# Micro.net
KiCad netlist of a schematic drawn in Altium Designer
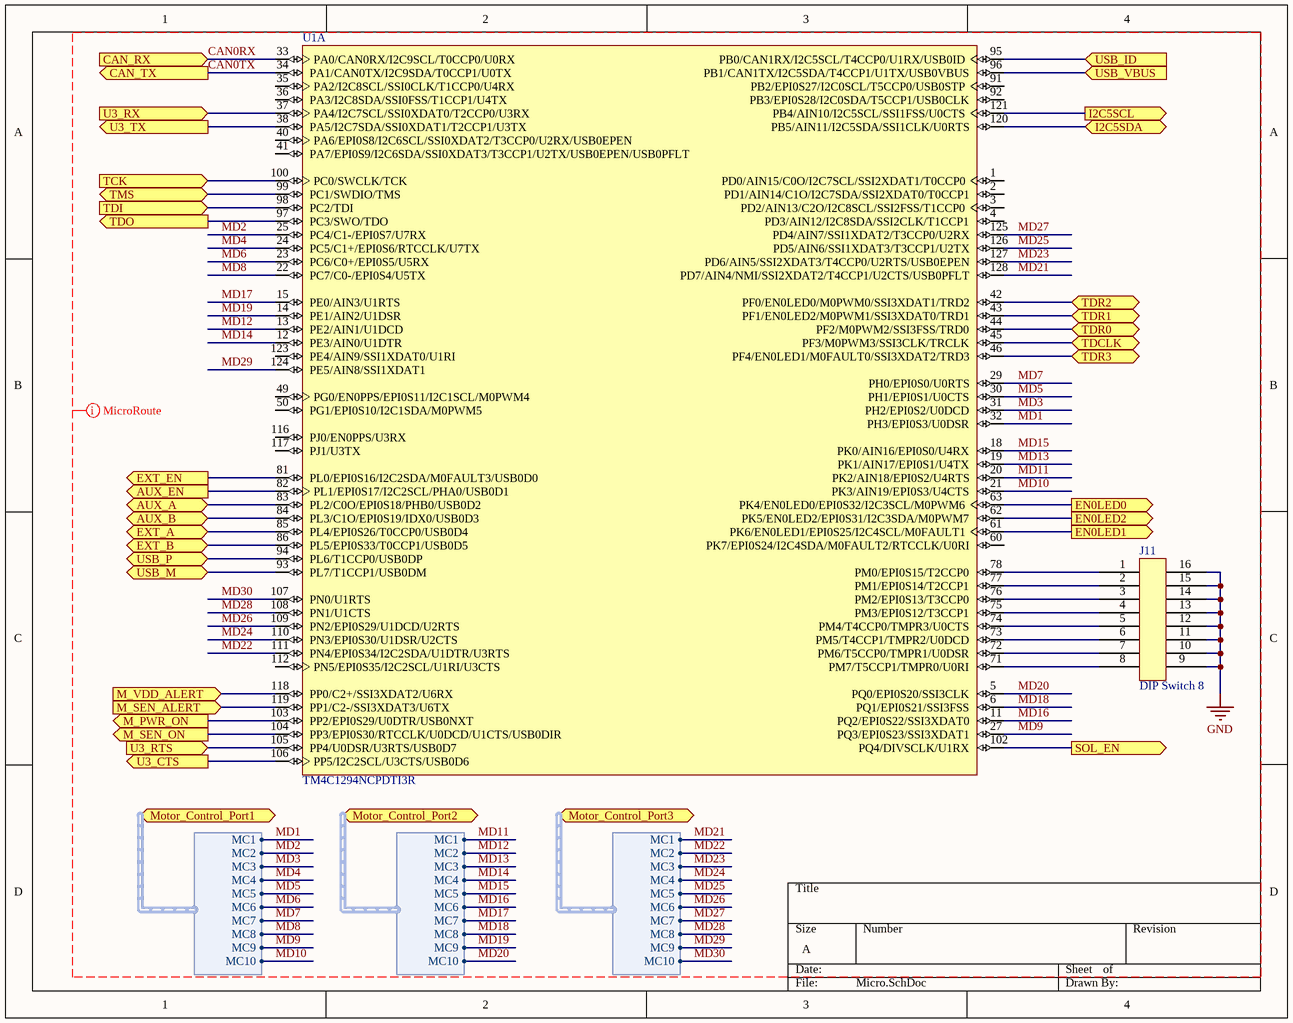
[diagram p0: Micro.SchDoc]

(export (version "E")
  (design (tool "Eeschema 10.0.6"))
  (components
    (comp (ref "J11") (value "DIP Switch 8") (footprint "DIP8") (libsource (lib "HSBNE-MAIN") (part "DIP8")))
    (comp (ref "U1")
      (value "TM4C1294NCPDTI3R")
      (footprint "TI-PDT128_M")
      (fields (field (name "MANUFACTURER") "Texas Instruments"))
      (libsource (lib "Altium Inc") (part "TI-TM4C1294NCPDT-128"))
    )
  )
  (nets
    (net (code "2") (name "/AUX_A") (class "Default")
      (node (ref "U1") (pin "83") (pinfunction "PL2/C0O/EPI0S18/PHB0/USB0D2_83") (pintype "bidirectional"))
    )
    (net (code "3") (name "/AUX_B") (class "Default")
      (node (ref "U1") (pin "84") (pinfunction "PL3/C1O/EPI0S19/IDX0/USB0D3_84") (pintype "bidirectional"))
    )
    (net (code "4") (name "/AUX_EN") (class "Default")
      (node (ref "U1") (pin "82") (pinfunction "PL1/EPI0S17/I2C2SCL/PHA0/USB0D1_82") (pintype "bidirectional"))
    )
    (net (code "5") (name "/CAN0RX") (class "Default")
      (node (ref "U1") (pin "33") (pinfunction "PA0/CAN0RX/I2C9SCL/T0CCP0/U0RX_33") (pintype "bidirectional"))
    )
    (net (code "6") (name "/CAN0TX") (class "Default")
      (node (ref "U1") (pin "34") (pinfunction "PA1/CAN0TX/I2C9SDA/T0CCP1/U0TX_34") (pintype "bidirectional"))
    )
    (net (code "7") (name "/EN0LED0") (class "Default")
      (node (ref "U1") (pin "63") (pinfunction "PK4/EN0LED0/EPI0S32/I2C3SCL/M0PWM6_63") (pintype "bidirectional"))
    )
    (net (code "8") (name "/EN0LED1") (class "Default")
      (node (ref "U1") (pin "61") (pinfunction "PK6/EN0LED1/EPI0S25/I2C4SCL/M0FAULT1_61") (pintype "bidirectional"))
    )
    (net (code "9") (name "/EN0LED2") (class "Default")
      (node (ref "U1") (pin "62") (pinfunction "PK5/EN0LED2/EPI0S31/I2C3SDA/M0PWM7_62") (pintype "bidirectional"))
    )
    (net (code "10") (name "/EXT_A") (class "Default")
      (node (ref "U1") (pin "85") (pinfunction "PL4/EPI0S26/T0CCP0/USB0D4_85") (pintype "bidirectional"))
    )
    (net (code "11") (name "/EXT_B") (class "Default")
      (node (ref "U1") (pin "86") (pinfunction "PL5/EPI0S33/T0CCP1/USB0D5_86") (pintype "bidirectional"))
    )
    (net (code "12") (name "/EXT_EN") (class "Default")
      (node (ref "U1") (pin "81") (pinfunction "PL0/EPI0S16/I2C2SDA/M0FAULT3/USB0D0_81") (pintype "bidirectional"))
    )
    (net (code "13") (name "/I2C5SCL") (class "Default")
      (node (ref "U1") (pin "121") (pinfunction "PB4/AIN10/I2C5SCL/SSI1FSS/U0CTS_121") (pintype "bidirectional"))
    )
    (net (code "14") (name "/I2C5SDA") (class "Default")
      (node (ref "U1") (pin "120") (pinfunction "PB5/AIN11/I2C5SDA/SSI1CLK/U0RTS_120") (pintype "bidirectional"))
    )
    (net (code "15") (name "/MD1") (class "Default")
      (node (ref "U1") (pin "32") (pinfunction "PH3/EPI0S3/U0DSR_32") (pintype "bidirectional"))
    )
    (net (code "16") (name "/MD2") (class "Default")
      (node (ref "U1") (pin "25") (pinfunction "PC4/C1-/EPI0S7/U7RX_25") (pintype "bidirectional"))
    )
    (net (code "17") (name "/MD3") (class "Default")
      (node (ref "U1") (pin "31") (pinfunction "PH2/EPI0S2/U0DCD_31") (pintype "bidirectional"))
    )
    (net (code "18") (name "/MD4") (class "Default")
      (node (ref "U1") (pin "24") (pinfunction "PC5/C1+/EPI0S6/RTCCLK/U7TX_24") (pintype "bidirectional"))
    )
    (net (code "19") (name "/MD5") (class "Default")
      (node (ref "U1") (pin "30") (pinfunction "PH1/EPI0S1/U0CTS_30") (pintype "bidirectional"))
    )
    (net (code "20") (name "/MD6") (class "Default")
      (node (ref "U1") (pin "23") (pinfunction "PC6/C0+/EPI0S5/U5RX_23") (pintype "bidirectional"))
    )
    (net (code "21") (name "/MD7") (class "Default")
      (node (ref "U1") (pin "29") (pinfunction "PH0/EPI0S0/U0RTS_29") (pintype "bidirectional"))
    )
    (net (code "22") (name "/MD8") (class "Default")
      (node (ref "U1") (pin "22") (pinfunction "PC7/C0-/EPI0S4/U5TX_22") (pintype "bidirectional"))
    )
    (net (code "23") (name "/MD9") (class "Default")
      (node (ref "U1") (pin "27") (pinfunction "PQ3/EPI0S23/SSI3XDAT1_27") (pintype "bidirectional"))
    )
    (net (code "24") (name "/MD10") (class "Default")
      (node (ref "U1") (pin "21") (pinfunction "PK3/AIN19/EPI0S3/U4CTS_21") (pintype "bidirectional"))
    )
    (net (code "25") (name "/MD11") (class "Default")
      (node (ref "U1") (pin "20") (pinfunction "PK2/AIN18/EPI0S2/U4RTS_20") (pintype "bidirectional"))
    )
    (net (code "26") (name "/MD12") (class "Default")
      (node (ref "U1") (pin "13") (pinfunction "PE2/AIN1/U1DCD_13") (pintype "bidirectional"))
    )
    (net (code "27") (name "/MD13") (class "Default")
      (node (ref "U1") (pin "19") (pinfunction "PK1/AIN17/EPI0S1/U4TX_19") (pintype "bidirectional"))
    )
    (net (code "28") (name "/MD14") (class "Default")
      (node (ref "U1") (pin "12") (pinfunction "PE3/AIN0/U1DTR_12") (pintype "bidirectional"))
    )
    (net (code "29") (name "/MD15") (class "Default")
      (node (ref "U1") (pin "18") (pinfunction "PK0/AIN16/EPI0S0/U4RX_18") (pintype "bidirectional"))
    )
    (net (code "30") (name "/MD16") (class "Default")
      (node (ref "U1") (pin "11") (pinfunction "PQ2/EPI0S22/SSI3XDAT0_11") (pintype "bidirectional"))
    )
    (net (code "31") (name "/MD17") (class "Default")
      (node (ref "U1") (pin "15") (pinfunction "PE0/AIN3/U1RTS_15") (pintype "bidirectional"))
    )
    (net (code "32") (name "/MD18") (class "Default")
      (node (ref "U1") (pin "6") (pinfunction "PQ1/EPI0S21/SSI3FSS_6") (pintype "bidirectional"))
    )
    (net (code "33") (name "/MD19") (class "Default")
      (node (ref "U1") (pin "14") (pinfunction "PE1/AIN2/U1DSR_14") (pintype "bidirectional"))
    )
    (net (code "34") (name "/MD20") (class "Default")
      (node (ref "U1") (pin "5") (pinfunction "PQ0/EPI0S20/SSI3CLK_5") (pintype "bidirectional"))
    )
    (net (code "35") (name "/MD21") (class "Default")
      (node (ref "U1") (pin "128") (pinfunction "PD7/AIN4/NMI/SSI2XDAT2/T4CCP1/U2CTS/USB0PFLT_128") (pintype "bidirectional"))
    )
    (net (code "36") (name "/MD22") (class "Default")
      (node (ref "U1") (pin "111") (pinfunction "PN4/EPI0S34/I2C2SDA/U1DTR/U3RTS_111") (pintype "bidirectional"))
    )
    (net (code "37") (name "/MD23") (class "Default")
      (node (ref "U1") (pin "127") (pinfunction "PD6/AIN5/SSI2XDAT3/T4CCP0/U2RTS/USB0EPEN_127") (pintype "bidirectional"))
    )
    (net (code "38") (name "/MD24") (class "Default")
      (node (ref "U1") (pin "110") (pinfunction "PN3/EPI0S30/U1DSR/U2CTS_110") (pintype "bidirectional"))
    )
    (net (code "39") (name "/MD25") (class "Default")
      (node (ref "U1") (pin "126") (pinfunction "PD5/AIN6/SSI1XDAT3/T3CCP1/U2TX_126") (pintype "bidirectional"))
    )
    (net (code "40") (name "/MD26") (class "Default")
      (node (ref "U1") (pin "109") (pinfunction "PN2/EPI0S29/U1DCD/U2RTS_109") (pintype "bidirectional"))
    )
    (net (code "41") (name "/MD27") (class "Default")
      (node (ref "U1") (pin "125") (pinfunction "PD4/AIN7/SSI1XDAT2/T3CCP0/U2RX_125") (pintype "bidirectional"))
    )
    (net (code "42") (name "/MD28") (class "Default")
      (node (ref "U1") (pin "108") (pinfunction "PN1/U1CTS_108") (pintype "bidirectional"))
    )
    (net (code "43") (name "/MD29") (class "Default")
      (node (ref "U1") (pin "124") (pinfunction "PE5/AIN8/SSI1XDAT1_124") (pintype "bidirectional"))
    )
    (net (code "44") (name "/MD30") (class "Default")
      (node (ref "U1") (pin "107") (pinfunction "PN0/U1RTS_107") (pintype "bidirectional"))
    )
    (net (code "45") (name "/M_PWR_ON") (class "Default")
      (node (ref "U1") (pin "103") (pinfunction "PP2/EPI0S29/U0DTR/USB0NXT_103") (pintype "bidirectional"))
    )
    (net (code "46") (name "/M_SEN_ALERT") (class "Default")
      (node (ref "U1") (pin "119") (pinfunction "PP1/C2-/SSI3XDAT3/U6TX_119") (pintype "bidirectional"))
    )
    (net (code "47") (name "/M_SEN_ON") (class "Default")
      (node (ref "U1") (pin "104") (pinfunction "PP3/EPI0S30/RTCCLK/U0DCD/U1CTS/USB0DIR_104") (pintype "bidirectional"))
    )
    (net (code "48") (name "/M_VDD_ALERT") (class "Default")
      (node (ref "U1") (pin "118") (pinfunction "PP0/C2+/SSI3XDAT2/U6RX_118") (pintype "bidirectional"))
    )
    (net (code "49") (name "/SOL_EN") (class "Default")
      (node (ref "U1") (pin "102") (pinfunction "PQ4/DIVSCLK/U1RX_102") (pintype "bidirectional"))
    )
    (net (code "50") (name "/TCK") (class "Default")
      (node (ref "U1") (pin "100") (pinfunction "PC0/SWCLK/TCK_100") (pintype "bidirectional"))
    )
    (net (code "51") (name "/TDCLK") (class "Default")
      (node (ref "U1") (pin "45") (pinfunction "PF3/M0PWM3/SSI3CLK/TRCLK_45") (pintype "bidirectional"))
    )
    (net (code "52") (name "/TDI") (class "Default")
      (node (ref "U1") (pin "98") (pinfunction "PC2/TDI_98") (pintype "bidirectional"))
    )
    (net (code "53") (name "/TDO") (class "Default")
      (node (ref "U1") (pin "97") (pinfunction "PC3/SWO/TDO_97") (pintype "bidirectional"))
    )
    (net (code "54") (name "/TDR0") (class "Default")
      (node (ref "U1") (pin "44") (pinfunction "PF2/M0PWM2/SSI3FSS/TRD0_44") (pintype "bidirectional"))
    )
    (net (code "55") (name "/TDR1") (class "Default")
      (node (ref "U1") (pin "43") (pinfunction "PF1/EN0LED2/M0PWM1/SSI3XDAT0/TRD1_43") (pintype "bidirectional"))
    )
    (net (code "56") (name "/TDR2") (class "Default")
      (node (ref "U1") (pin "42") (pinfunction "PF0/EN0LED0/M0PWM0/SSI3XDAT1/TRD2_42") (pintype "bidirectional"))
    )
    (net (code "57") (name "/TDR3") (class "Default")
      (node (ref "U1") (pin "46") (pinfunction "PF4/EN0LED1/M0FAULT0/SSI3XDAT2/TRD3_46") (pintype "bidirectional"))
    )
    (net (code "58") (name "/TMS") (class "Default")
      (node (ref "U1") (pin "99") (pinfunction "PC1/SWDIO/TMS_99") (pintype "bidirectional"))
    )
    (net (code "59") (name "/U3_CTS") (class "Default")
      (node (ref "U1") (pin "106") (pinfunction "PP5/I2C2SCL/U3CTS/USB0D6_106") (pintype "bidirectional"))
    )
    (net (code "60") (name "/U3_RTS") (class "Default")
      (node (ref "U1") (pin "105") (pinfunction "PP4/U0DSR/U3RTS/USB0D7_105") (pintype "bidirectional"))
    )
    (net (code "61") (name "/U3_RX") (class "Default")
      (node (ref "U1") (pin "37") (pinfunction "PA4/I2C7SCL/SSI0XDAT0/T2CCP0/U3RX_37") (pintype "bidirectional"))
    )
    (net (code "62") (name "/U3_TX") (class "Default")
      (node (ref "U1") (pin "38") (pinfunction "PA5/I2C7SDA/SSI0XDAT1/T2CCP1/U3TX_38") (pintype "bidirectional"))
    )
    (net (code "63") (name "/USB_ID") (class "Default")
      (node (ref "U1") (pin "95") (pinfunction "PB0/CAN1RX/I2C5SCL/T4CCP0/U1RX/USB0ID_95") (pintype "bidirectional"))
    )
    (net (code "64") (name "/USB_M") (class "Default")
      (node (ref "U1") (pin "93") (pinfunction "PL7/T1CCP1/USB0DM_93") (pintype "bidirectional"))
    )
    (net (code "65") (name "/USB_P") (class "Default")
      (node (ref "U1") (pin "94") (pinfunction "PL6/T1CCP0/USB0DP_94") (pintype "bidirectional"))
    )
    (net (code "66") (name "/USB_VBUS") (class "Default")
      (node (ref "U1") (pin "96") (pinfunction "PB1/CAN1TX/I2C5SDA/T4CCP1/U1TX/USB0VBUS_96") (pintype "bidirectional"))
    )
    (net (code "68") (name "GND") (class "Default")
      (node (ref "J11") (pin "10") (pinfunction "10_10") (pintype "passive"))
      (node (ref "J11") (pin "11") (pinfunction "11_11") (pintype "passive"))
      (node (ref "J11") (pin "12") (pinfunction "12_12") (pintype "passive"))
      (node (ref "J11") (pin "13") (pinfunction "13_13") (pintype "passive"))
      (node (ref "J11") (pin "14") (pinfunction "14_14") (pintype "passive"))
      (node (ref "J11") (pin "15") (pinfunction "15_15") (pintype "passive"))
      (node (ref "J11") (pin "16") (pinfunction "16_16") (pintype "passive"))
      (node (ref "J11") (pin "9") (pinfunction "9_9") (pintype "passive"))
    )
    (net (code "69") (name "Net-(U1A-PM0{slash}EPI0S15{slash}T2CCP0)") (class "Default")
      (node (ref "J11") (pin "1") (pinfunction "1_1") (pintype "passive"))
      (node (ref "U1") (pin "78") (pinfunction "PM0/EPI0S15/T2CCP0_78") (pintype "bidirectional"))
    )
    (net (code "70") (name "Net-(U1A-PM1{slash}EPI0S14{slash}T2CCP1)") (class "Default")
      (node (ref "J11") (pin "2") (pinfunction "2_2") (pintype "passive"))
      (node (ref "U1") (pin "77") (pinfunction "PM1/EPI0S14/T2CCP1_77") (pintype "bidirectional"))
    )
    (net (code "71") (name "Net-(U1A-PM2{slash}EPI0S13{slash}T3CCP0)") (class "Default")
      (node (ref "J11") (pin "3") (pinfunction "3_3") (pintype "passive"))
      (node (ref "U1") (pin "76") (pinfunction "PM2/EPI0S13/T3CCP0_76") (pintype "bidirectional"))
    )
    (net (code "72") (name "Net-(U1A-PM3{slash}EPI0S12{slash}T3CCP1)") (class "Default")
      (node (ref "J11") (pin "4") (pinfunction "4_4") (pintype "passive"))
      (node (ref "U1") (pin "75") (pinfunction "PM3/EPI0S12/T3CCP1_75") (pintype "bidirectional"))
    )
    (net (code "73") (name "Net-(U1A-PM4{slash}T4CCP0{slash}TMPR3{slash}U0CTS)") (class "Default")
      (node (ref "J11") (pin "5") (pinfunction "5_5") (pintype "passive"))
      (node (ref "U1") (pin "74") (pinfunction "PM4/T4CCP0/TMPR3/U0CTS_74") (pintype "bidirectional"))
    )
    (net (code "74") (name "Net-(U1A-PM5{slash}T4CCP1{slash}TMPR2{slash}U0DCD)") (class "Default")
      (node (ref "J11") (pin "6") (pinfunction "6_6") (pintype "passive"))
      (node (ref "U1") (pin "73") (pinfunction "PM5/T4CCP1/TMPR2/U0DCD_73") (pintype "bidirectional"))
    )
    (net (code "75") (name "Net-(U1A-PM6{slash}T5CCP0{slash}TMPR1{slash}U0DSR)") (class "Default")
      (node (ref "J11") (pin "7") (pinfunction "7_7") (pintype "passive"))
      (node (ref "U1") (pin "72") (pinfunction "PM6/T5CCP0/TMPR1/U0DSR_72") (pintype "bidirectional"))
    )
    (net (code "76") (name "Net-(U1A-PM7{slash}T5CCP1{slash}TMPR0{slash}U0RI)") (class "Default")
      (node (ref "J11") (pin "8") (pinfunction "8_8") (pintype "passive"))
      (node (ref "U1") (pin "71") (pinfunction "PM7/T5CCP1/TMPR0/U0RI_71") (pintype "bidirectional"))
    )
    (net (code "77") (name "unconnected-(U1A-PA2{slash}I2C8SCL{slash}SSI0CLK{slash}T1CCP0{slash}U4RX-Pad35)") (class "Default")
      (node (ref "U1") (pin "35") (pinfunction "PA2/I2C8SCL/SSI0CLK/T1CCP0/U4RX_35") (pintype "bidirectional"))
    )
    (net (code "78") (name "unconnected-(U1A-PA3{slash}I2C8SDA{slash}SSI0FSS{slash}T1CCP1{slash}U4TX-Pad36)") (class "Default")
      (node (ref "U1") (pin "36") (pinfunction "PA3/I2C8SDA/SSI0FSS/T1CCP1/U4TX_36") (pintype "bidirectional"))
    )
    (net (code "79") (name "unconnected-(U1A-PA6{slash}EPI0S8{slash}I2C6SCL{slash}SSI0XDAT2{slash}T3CCP0{slash}U2RX{slash}USB0EPEN-Pad40)") (class "Default")
      (node (ref "U1") (pin "40") (pinfunction "PA6/EPI0S8/I2C6SCL/SSI0XDAT2/T3CCP0/U2RX/USB0EPEN_40") (pintype "bidirectional"))
    )
    (net (code "80") (name "unconnected-(U1A-PA7{slash}EPI0S9{slash}I2C6SDA{slash}SSI0XDAT3{slash}T3CCP1{slash}U2TX{slash}USB0EPEN{slash}USB0PFLT-Pad41)") (class "Default")
      (node (ref "U1") (pin "41") (pinfunction "PA7/EPI0S9/I2C6SDA/SSI0XDAT3/T3CCP1/U2TX/USB0EPEN/USB0PFLT_41") (pintype "bidirectional"))
    )
    (net (code "81") (name "unconnected-(U1A-PB2{slash}EPI0S27{slash}I2C0SCL{slash}T5CCP0{slash}USB0STP-Pad91)") (class "Default")
      (node (ref "U1") (pin "91") (pinfunction "PB2/EPI0S27/I2C0SCL/T5CCP0/USB0STP_91") (pintype "bidirectional"))
    )
    (net (code "82") (name "unconnected-(U1A-PB3{slash}EPI0S28{slash}I2C0SDA{slash}T5CCP1{slash}USB0CLK-Pad92)") (class "Default")
      (node (ref "U1") (pin "92") (pinfunction "PB3/EPI0S28/I2C0SDA/T5CCP1/USB0CLK_92") (pintype "bidirectional"))
    )
    (net (code "83") (name "unconnected-(U1A-PD0{slash}AIN15{slash}C0O{slash}I2C7SCL{slash}SSI2XDAT1{slash}T0CCP0-Pad1)") (class "Default")
      (node (ref "U1") (pin "1") (pinfunction "PD0/AIN15/C0O/I2C7SCL/SSI2XDAT1/T0CCP0_1") (pintype "bidirectional"))
    )
    (net (code "84") (name "unconnected-(U1A-PD1{slash}AIN14{slash}C1O{slash}I2C7SDA{slash}SSI2XDAT0{slash}T0CCP1-Pad2)") (class "Default")
      (node (ref "U1") (pin "2") (pinfunction "PD1/AIN14/C1O/I2C7SDA/SSI2XDAT0/T0CCP1_2") (pintype "bidirectional"))
    )
    (net (code "85") (name "unconnected-(U1A-PD2{slash}AIN13{slash}C2O{slash}I2C8SCL{slash}SSI2FSS{slash}T1CCP0-Pad3)") (class "Default")
      (node (ref "U1") (pin "3") (pinfunction "PD2/AIN13/C2O/I2C8SCL/SSI2FSS/T1CCP0_3") (pintype "bidirectional"))
    )
    (net (code "86") (name "unconnected-(U1A-PD3{slash}AIN12{slash}I2C8SDA{slash}SSI2CLK{slash}T1CCP1-Pad4)") (class "Default")
      (node (ref "U1") (pin "4") (pinfunction "PD3/AIN12/I2C8SDA/SSI2CLK/T1CCP1_4") (pintype "bidirectional"))
    )
    (net (code "87") (name "unconnected-(U1A-PE4{slash}AIN9{slash}SSI1XDAT0{slash}U1RI-Pad123)") (class "Default")
      (node (ref "U1") (pin "123") (pinfunction "PE4/AIN9/SSI1XDAT0/U1RI_123") (pintype "bidirectional"))
    )
    (net (code "88") (name "unconnected-(U1A-PG0{slash}EN0PPS{slash}EPI0S11{slash}I2C1SCL{slash}M0PWM4-Pad49)") (class "Default")
      (node (ref "U1") (pin "49") (pinfunction "PG0/EN0PPS/EPI0S11/I2C1SCL/M0PWM4_49") (pintype "bidirectional"))
    )
    (net (code "89") (name "unconnected-(U1A-PG1{slash}EPI0S10{slash}I2C1SDA{slash}M0PWM5-Pad50)") (class "Default")
      (node (ref "U1") (pin "50") (pinfunction "PG1/EPI0S10/I2C1SDA/M0PWM5_50") (pintype "bidirectional"))
    )
    (net (code "90") (name "unconnected-(U1A-PJ0{slash}EN0PPS{slash}U3RX-Pad116)") (class "Default")
      (node (ref "U1") (pin "116") (pinfunction "PJ0/EN0PPS/U3RX_116") (pintype "bidirectional"))
    )
    (net (code "91") (name "unconnected-(U1A-PJ1{slash}U3TX-Pad117)") (class "Default")
      (node (ref "U1") (pin "117") (pinfunction "PJ1/U3TX_117") (pintype "bidirectional"))
    )
    (net (code "92") (name "unconnected-(U1A-PK7{slash}EPI0S24{slash}I2C4SDA{slash}M0FAULT2{slash}RTCCLK{slash}U0RI-Pad60)") (class "Default")
      (node (ref "U1") (pin "60") (pinfunction "PK7/EPI0S24/I2C4SDA/M0FAULT2/RTCCLK/U0RI_60") (pintype "bidirectional"))
    )
    (net (code "93") (name "unconnected-(U1A-PN5{slash}EPI0S35{slash}I2C2SCL{slash}U1RI{slash}U3CTS-Pad112)") (class "Default")
      (node (ref "U1") (pin "112") (pinfunction "PN5/EPI0S35/I2C2SCL/U1RI/U3CTS_112") (pintype "bidirectional"))
    )
  )
)
